# pannel_24_v5.net
KiCad netlist of a schematic drawn in EAGLE
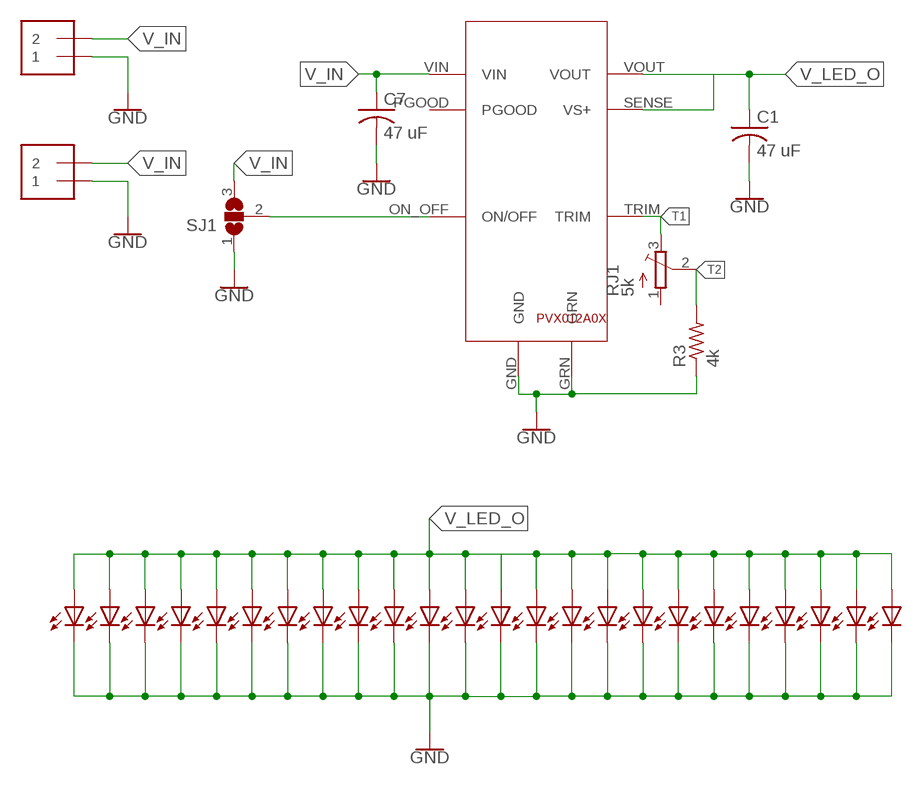
[diagram p0: schematic, sheet 1]

(export (version "E")
  (design (tool "Eeschema 10.0.6"))
  (components
    (comp (ref "C1")
      (value "47 uF")
      (footprint "eagle-import:C1210")
      (libsource (lib "eagle-import") (part "C-USC1210"))
    )
    (comp (ref "C7")
      (value "47 uF")
      (footprint "eagle-import:C1210")
      (libsource (lib "eagle-import") (part "C-USC1210"))
    )
    (comp (ref "R3")
      (value "4k")
      (footprint "eagle-import:R0603")
      (libsource (lib "eagle-import") (part "R-US_R0603"))
    )
    (comp (ref "RJ1")
      (value "5k")
      (footprint "eagle-import:3223W")
      (libsource (lib "eagle-import") (part "TRIM_EU-3223W"))
    )
    (comp (ref "SJ1")
      (value "SJ2W")
      (footprint "eagle-import:SJ_2")
      (libsource (lib "eagle-import") (part "SJ2W"))
    )
    (comp (ref "U$1")
      (value "LED")
      (footprint "eagle-import:3WLED")
      (libsource (lib "eagle-import") (part "LED"))
    )
    (comp (ref "U$2")
      (value "LED")
      (footprint "eagle-import:3WLED")
      (libsource (lib "eagle-import") (part "LED"))
    )
    (comp (ref "U$3")
      (value "LED")
      (footprint "eagle-import:3WLED")
      (libsource (lib "eagle-import") (part "LED"))
    )
    (comp (ref "U$4")
      (value "LED")
      (footprint "eagle-import:3WLED")
      (libsource (lib "eagle-import") (part "LED"))
    )
    (comp (ref "U$5")
      (value "LED")
      (footprint "eagle-import:3WLED")
      (libsource (lib "eagle-import") (part "LED"))
    )
    (comp (ref "U$6")
      (value "LED")
      (footprint "eagle-import:3WLED")
      (libsource (lib "eagle-import") (part "LED"))
    )
    (comp (ref "U$7")
      (value "LED")
      (footprint "eagle-import:3WLED")
      (libsource (lib "eagle-import") (part "LED"))
    )
    (comp (ref "U$8")
      (value "LED")
      (footprint "eagle-import:3WLED")
      (libsource (lib "eagle-import") (part "LED"))
    )
    (comp (ref "U$9")
      (value "LED")
      (footprint "eagle-import:3WLED")
      (libsource (lib "eagle-import") (part "LED"))
    )
    (comp (ref "U$10")
      (value "LED")
      (footprint "eagle-import:3WLED")
      (libsource (lib "eagle-import") (part "LED"))
    )
    (comp (ref "U$11")
      (value "LED")
      (footprint "eagle-import:3WLED")
      (libsource (lib "eagle-import") (part "LED"))
    )
    (comp (ref "U$12")
      (value "LED")
      (footprint "eagle-import:3WLED")
      (libsource (lib "eagle-import") (part "LED"))
    )
    (comp (ref "U$13")
      (value "LED")
      (footprint "eagle-import:3WLED")
      (libsource (lib "eagle-import") (part "LED"))
    )
    (comp (ref "U$14")
      (value "LED")
      (footprint "eagle-import:3WLED")
      (libsource (lib "eagle-import") (part "LED"))
    )
    (comp (ref "U$15")
      (value "LED")
      (footprint "eagle-import:3WLED")
      (libsource (lib "eagle-import") (part "LED"))
    )
    (comp (ref "U$16")
      (value "LED")
      (footprint "eagle-import:3WLED")
      (libsource (lib "eagle-import") (part "LED"))
    )
    (comp (ref "U$17")
      (value "LED")
      (footprint "eagle-import:3WLED")
      (libsource (lib "eagle-import") (part "LED"))
    )
    (comp (ref "U$18")
      (value "LED")
      (footprint "eagle-import:3WLED")
      (libsource (lib "eagle-import") (part "LED"))
    )
    (comp (ref "U$19")
      (value "LED")
      (footprint "eagle-import:3WLED")
      (libsource (lib "eagle-import") (part "LED"))
    )
    (comp (ref "U$20")
      (value "LED")
      (footprint "eagle-import:3WLED")
      (libsource (lib "eagle-import") (part "LED"))
    )
    (comp (ref "U$21")
      (value "LED")
      (footprint "eagle-import:3WLED")
      (libsource (lib "eagle-import") (part "LED"))
    )
    (comp (ref "U$22")
      (value "LED")
      (footprint "eagle-import:3WLED")
      (libsource (lib "eagle-import") (part "LED"))
    )
    (comp (ref "U$23")
      (value "LED")
      (footprint "eagle-import:3WLED")
      (libsource (lib "eagle-import") (part "LED"))
    )
    (comp (ref "U$24")
      (value "LED")
      (footprint "eagle-import:3WLED")
      (libsource (lib "eagle-import") (part "LED"))
    )
    (comp (ref "U$25")
      (value "PVX012A0XV1")
      (footprint "eagle-import:PVX012A0X")
      (libsource (lib "eagle-import") (part "PVX012A0XV1"))
    )
    (comp (ref "U$26")
      (value "MOLEX_0039301022")
      (footprint "eagle-import:MINI-FIT_JR_CONN")
      (libsource (lib "eagle-import") (part "MOLEX_0039301022"))
    )
    (comp (ref "U$27")
      (value "MOLEX_0039301022")
      (footprint "eagle-import:MINI-FIT_JR_CONN")
      (libsource (lib "eagle-import") (part "MOLEX_0039301022"))
    )
  )
  (nets
    (net (code "1") (name "GND") (class "Default")
      (node (ref "C1") (pin "2") (pinfunction "2_2") (pintype "passive"))
      (node (ref "C7") (pin "2") (pinfunction "2_2") (pintype "passive"))
      (node (ref "R3") (pin "1") (pinfunction "1_1") (pintype "passive"))
      (node (ref "SJ1") (pin "1") (pinfunction "1_1") (pintype "passive"))
      (node (ref "U$1") (pin "P$2") (pinfunction "C_P$2") (pintype "passive"))
      (node (ref "U$10") (pin "P$2") (pinfunction "C_P$2") (pintype "passive"))
      (node (ref "U$11") (pin "P$2") (pinfunction "C_P$2") (pintype "passive"))
      (node (ref "U$12") (pin "P$2") (pinfunction "C_P$2") (pintype "passive"))
      (node (ref "U$13") (pin "P$2") (pinfunction "C_P$2") (pintype "passive"))
      (node (ref "U$14") (pin "P$2") (pinfunction "C_P$2") (pintype "passive"))
      (node (ref "U$15") (pin "P$2") (pinfunction "C_P$2") (pintype "passive"))
      (node (ref "U$16") (pin "P$2") (pinfunction "C_P$2") (pintype "passive"))
      (node (ref "U$17") (pin "P$2") (pinfunction "C_P$2") (pintype "passive"))
      (node (ref "U$18") (pin "P$2") (pinfunction "C_P$2") (pintype "passive"))
      (node (ref "U$19") (pin "P$2") (pinfunction "C_P$2") (pintype "passive"))
      (node (ref "U$2") (pin "P$2") (pinfunction "C_P$2") (pintype "passive"))
      (node (ref "U$20") (pin "P$2") (pinfunction "C_P$2") (pintype "passive"))
      (node (ref "U$21") (pin "P$2") (pinfunction "C_P$2") (pintype "passive"))
      (node (ref "U$22") (pin "P$2") (pinfunction "C_P$2") (pintype "passive"))
      (node (ref "U$23") (pin "P$2") (pinfunction "C_P$2") (pintype "passive"))
      (node (ref "U$24") (pin "P$2") (pinfunction "C_P$2") (pintype "passive"))
      (node (ref "U$25") (pin "GND") (pinfunction "GND_GND") (pintype "bidirectional"))
      (node (ref "U$25") (pin "GRN") (pinfunction "GRN_GRN") (pintype "bidirectional"))
      (node (ref "U$26") (pin "P$2") (pinfunction "1_P$2") (pintype "passive"))
      (node (ref "U$27") (pin "P$2") (pinfunction "1_P$2") (pintype "passive"))
      (node (ref "U$3") (pin "P$2") (pinfunction "C_P$2") (pintype "passive"))
      (node (ref "U$4") (pin "P$2") (pinfunction "C_P$2") (pintype "passive"))
      (node (ref "U$5") (pin "P$2") (pinfunction "C_P$2") (pintype "passive"))
      (node (ref "U$6") (pin "P$2") (pinfunction "C_P$2") (pintype "passive"))
      (node (ref "U$7") (pin "P$2") (pinfunction "C_P$2") (pintype "passive"))
      (node (ref "U$8") (pin "P$2") (pinfunction "C_P$2") (pintype "passive"))
      (node (ref "U$9") (pin "P$2") (pinfunction "C_P$2") (pintype "passive"))
    )
    (net (code "2") (name "Net-(U$25-ON{slash}OFF)") (class "Default")
      (node (ref "SJ1") (pin "2") (pinfunction "2_2") (pintype "passive"))
      (node (ref "U$25") (pin "ON_OFF") (pinfunction "ON/OFF_ON_OFF") (pintype "bidirectional"))
    )
    (net (code "3") (name "T1") (class "Default")
      (node (ref "RJ1") (pin "3") (pinfunction "E_3") (pintype "passive"))
      (node (ref "U$25") (pin "TRIM") (pinfunction "TRIM_TRIM") (pintype "bidirectional"))
    )
    (net (code "4") (name "T2") (class "Default")
      (node (ref "R3") (pin "2") (pinfunction "2_2") (pintype "passive"))
      (node (ref "RJ1") (pin "2") (pinfunction "S_2") (pintype "passive"))
    )
    (net (code "5") (name "V_IN") (class "Default")
      (node (ref "C7") (pin "1") (pinfunction "1_1") (pintype "passive"))
      (node (ref "SJ1") (pin "3") (pinfunction "3_3") (pintype "passive"))
      (node (ref "U$25") (pin "VIN") (pinfunction "VIN_VIN") (pintype "bidirectional"))
      (node (ref "U$26") (pin "P$1") (pinfunction "2_P$1") (pintype "passive"))
      (node (ref "U$27") (pin "P$1") (pinfunction "2_P$1") (pintype "passive"))
    )
    (net (code "6") (name "V_LED_O") (class "Default")
      (node (ref "C1") (pin "1") (pinfunction "1_1") (pintype "passive"))
      (node (ref "U$1") (pin "P$1") (pinfunction "A_P$1") (pintype "passive"))
      (node (ref "U$10") (pin "P$1") (pinfunction "A_P$1") (pintype "passive"))
      (node (ref "U$11") (pin "P$1") (pinfunction "A_P$1") (pintype "passive"))
      (node (ref "U$12") (pin "P$1") (pinfunction "A_P$1") (pintype "passive"))
      (node (ref "U$13") (pin "P$1") (pinfunction "A_P$1") (pintype "passive"))
      (node (ref "U$14") (pin "P$1") (pinfunction "A_P$1") (pintype "passive"))
      (node (ref "U$15") (pin "P$1") (pinfunction "A_P$1") (pintype "passive"))
      (node (ref "U$16") (pin "P$1") (pinfunction "A_P$1") (pintype "passive"))
      (node (ref "U$17") (pin "P$1") (pinfunction "A_P$1") (pintype "passive"))
      (node (ref "U$18") (pin "P$1") (pinfunction "A_P$1") (pintype "passive"))
      (node (ref "U$19") (pin "P$1") (pinfunction "A_P$1") (pintype "passive"))
      (node (ref "U$2") (pin "P$1") (pinfunction "A_P$1") (pintype "passive"))
      (node (ref "U$20") (pin "P$1") (pinfunction "A_P$1") (pintype "passive"))
      (node (ref "U$21") (pin "P$1") (pinfunction "A_P$1") (pintype "passive"))
      (node (ref "U$22") (pin "P$1") (pinfunction "A_P$1") (pintype "passive"))
      (node (ref "U$23") (pin "P$1") (pinfunction "A_P$1") (pintype "passive"))
      (node (ref "U$24") (pin "P$1") (pinfunction "A_P$1") (pintype "passive"))
      (node (ref "U$25") (pin "SENSE") (pinfunction "VS+_SENSE") (pintype "bidirectional"))
      (node (ref "U$25") (pin "VOUT") (pinfunction "VOUT_VOUT") (pintype "bidirectional"))
      (node (ref "U$3") (pin "P$1") (pinfunction "A_P$1") (pintype "passive"))
      (node (ref "U$4") (pin "P$1") (pinfunction "A_P$1") (pintype "passive"))
      (node (ref "U$5") (pin "P$1") (pinfunction "A_P$1") (pintype "passive"))
      (node (ref "U$6") (pin "P$1") (pinfunction "A_P$1") (pintype "passive"))
      (node (ref "U$7") (pin "P$1") (pinfunction "A_P$1") (pintype "passive"))
      (node (ref "U$8") (pin "P$1") (pinfunction "A_P$1") (pintype "passive"))
      (node (ref "U$9") (pin "P$1") (pinfunction "A_P$1") (pintype "passive"))
    )
    (net (code "7") (name "unconnected-(RJ1-A-Pad1)") (class "Default")
      (node (ref "RJ1") (pin "1") (pinfunction "A_1") (pintype "passive"))
    )
    (net (code "8") (name "unconnected-(U$25-PadPGOOD)") (class "Default")
      (node (ref "U$25") (pin "PGOOD") (pinfunction "PGOOD_PGOOD") (pintype "bidirectional"))
    )
  )
)
